# Reference_Voltage.net
KiCad netlist of a schematic drawn in Altium Designer
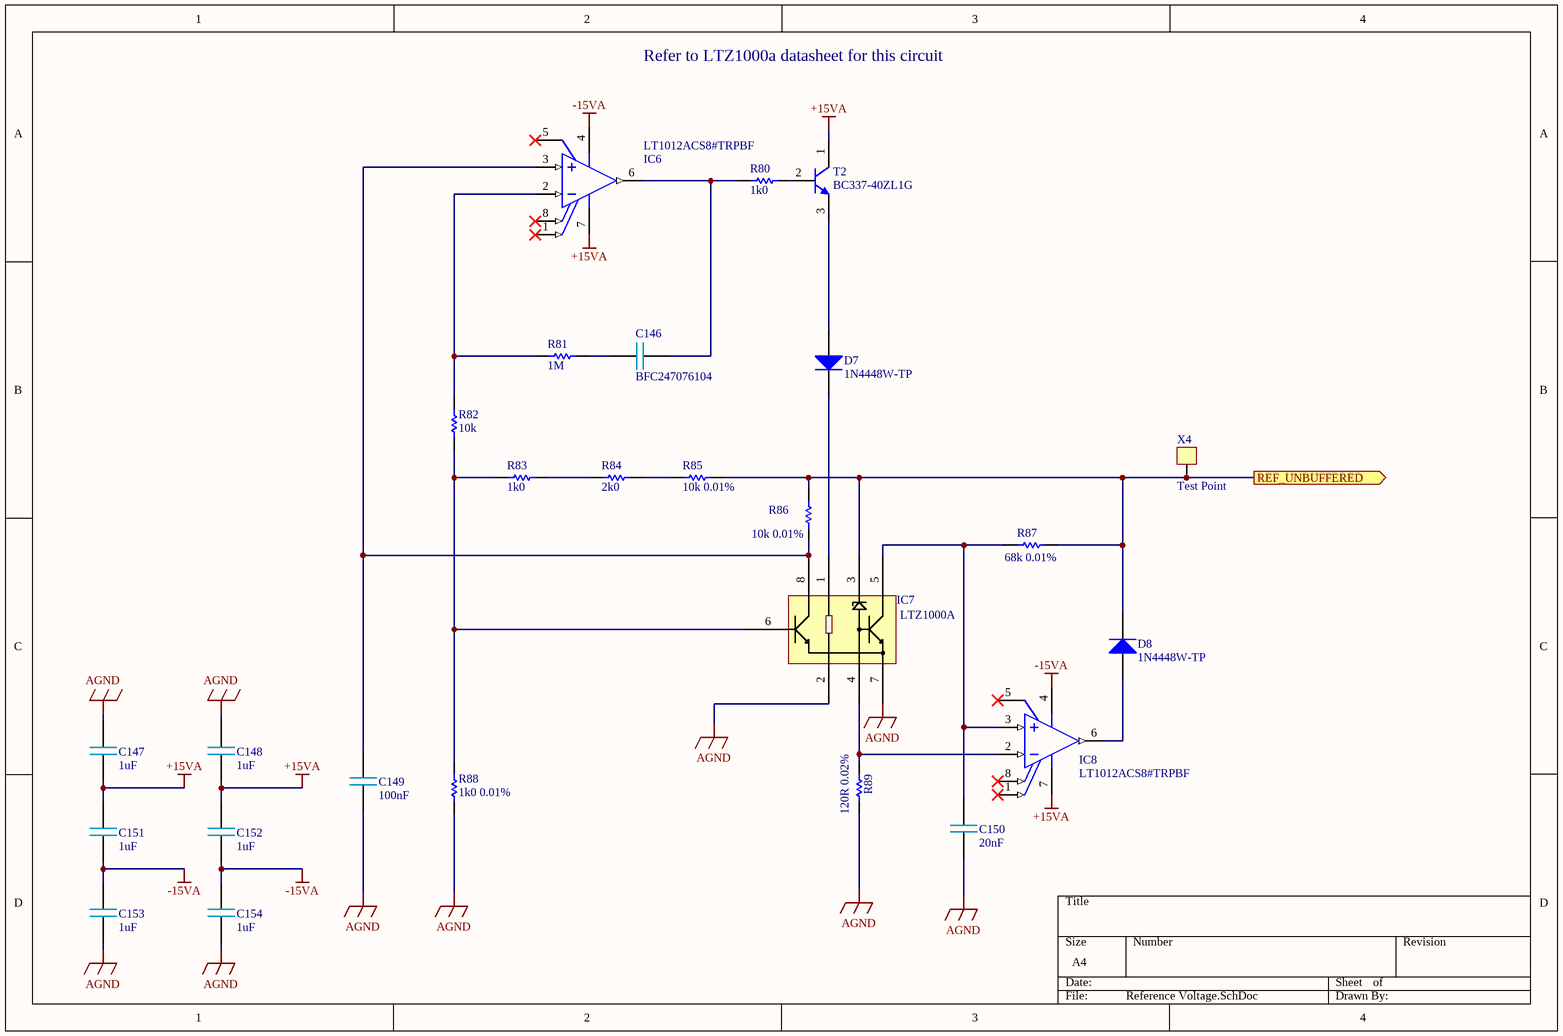
[diagram p0: Reference Voltage.SchDoc]

(export (version "E")
  (design (tool "Eeschema 10.0.6"))
  (components
    (comp (ref "C146")
      (value "BFC247076104")
      (footprint "Cap 5mm polyester")
      (libsource (lib "CurrentSource") (part "BFC247076104"))
    )
    (comp (ref "C147")
      (value "1uF")
      (footprint "Capacitor 7mmx3mm 5mm pitch")
      (libsource (lib "CurrentSource") (part "BFC247076104"))
    )
    (comp (ref "C148")
      (value "1uF")
      (footprint "Capacitor 7mmx3mm 5mm pitch")
      (libsource (lib "CurrentSource") (part "BFC247076104"))
    )
    (comp (ref "C149")
      (value "100nF")
      (footprint "Cap 5mm polyester")
      (libsource (lib "CurrentSource") (part "BFC247076104"))
    )
    (comp (ref "C150")
      (value "20nF")
      (footprint "Cap 5mm polyester")
      (libsource (lib "CurrentSource") (part "BFC247076104"))
    )
    (comp (ref "C151")
      (value "1uF")
      (footprint "Capacitor 7mmx3mm 5mm pitch")
      (libsource (lib "CurrentSource") (part "BFC247076104"))
    )
    (comp (ref "C152")
      (value "1uF")
      (footprint "Capacitor 7mmx3mm 5mm pitch")
      (libsource (lib "CurrentSource") (part "BFC247076104"))
    )
    (comp (ref "C153")
      (value "1uF")
      (footprint "Capacitor 7mmx3mm 5mm pitch")
      (libsource (lib "CurrentSource") (part "BFC247076104"))
    )
    (comp (ref "C154")
      (value "1uF")
      (footprint "Capacitor 7mmx3mm 5mm pitch")
      (libsource (lib "CurrentSource") (part "BFC247076104"))
    )
    (comp (ref "D7")
      (value "1N4448W-TP")
      (footprint "MCC-SOD123_V")
      (description "Switching Diode, 500 mW, 100 V, -55 to 150 degC, SOD123, RoHS, Tape and Reel")
      (fields (field (name "MANUFACTURER") "Micro Commercial Components"))
      (libsource (lib "Altium Content Vault") (part "CMP-0862-00001-1"))
    )
    (comp (ref "D8")
      (value "1N4448W-TP")
      (footprint "MCC-SOD123_V")
      (description "Switching Diode, 500 mW, 100 V, -55 to 150 degC, SOD123, RoHS, Tape and Reel")
      (fields (field (name "MANUFACTURER") "Micro Commercial Components"))
      (libsource (lib "Altium Content Vault") (part "CMP-0862-00001-1"))
    )
    (comp (ref "IC6")
      (value "LT1012ACS8#TRPBF")
      (footprint "LT-S8-8_M")
      (fields
        (field (name "LINEAR TECHNOLOGY PART NUMBER") "LT1012")
        (field (name "MANUFACTURER") "Linear Technology")
      )
      (libsource (lib "Altium Content Vault") (part "CMP-0359-03028-2"))
    )
    (comp (ref "IC7")
      (value "LTZ1000A")
      (footprint "H-08A")
      (libsource (lib "CurrentSource") (part "LTZ1000A"))
    )
    (comp (ref "IC8")
      (value "LT1012ACS8#TRPBF")
      (footprint "LT-S8-8_M")
      (fields
        (field (name "LINEAR TECHNOLOGY PART NUMBER") "LT1012")
        (field (name "MANUFACTURER") "Linear Technology")
      )
      (libsource (lib "Altium Content Vault") (part "CMP-0359-03028-2"))
    )
    (comp (ref "R80")
      (value "1k0")
      (footprint "RESC3116X65X40LL10T20")
      (fields (field (name "MANUFACTURER") "Yageo") (field (name "PART NUMBER") "RC1206FR-0710K2L"))
      (libsource (lib "Altium Content Vault") (part "CMP-2003-03538-1"))
    )
    (comp (ref "R81")
      (value "1M")
      (footprint "RESC0805(2012)_N")
      (description "1M 0.125W 1% 0805 (2012 Metric)  SMD")
      (fields (field (name "POWER") "0.125 W") (field (name "TOLERANCE") "1 %"))
      (libsource (lib "Altium Content Vault") (part "CMP-1013-00849-1"))
    )
    (comp (ref "R82")
      (value "10k")
      (footprint "RESC3116X65X40LL10T20")
      (fields (field (name "MANUFACTURER") "Yageo") (field (name "PART NUMBER") "RC1206FR-0710K2L"))
      (libsource (lib "Altium Content Vault") (part "CMP-2003-03538-1"))
    )
    (comp (ref "R83")
      (value "1k0")
      (footprint "RESC0805(2012)_N")
      (description "1M 0.125W 1% 0805 (2012 Metric)  SMD")
      (fields (field (name "POWER") "0.125 W") (field (name "TOLERANCE") "1 %"))
      (libsource (lib "Altium Content Vault") (part "CMP-1013-00849-1"))
    )
    (comp (ref "R84")
      (value "2k0")
      (footprint "RESC0805(2012)_N")
      (description "1M 0.125W 1% 0805 (2012 Metric)  SMD")
      (fields (field (name "POWER") "0.125 W") (field (name "TOLERANCE") "1 %"))
      (libsource (lib "Altium Content Vault") (part "CMP-1013-00849-1"))
    )
    (comp (ref "R85")
      (value "10k 0.01%")
      (footprint "RESC3116X65X40LL10T20")
      (fields (field (name "MANUFACTURER") "Yageo") (field (name "PART NUMBER") "RC1206FR-0710K2L"))
      (libsource (lib "Altium Content Vault") (part "CMP-2003-03538-1"))
    )
    (comp (ref "R86")
      (value "10k 0.01%")
      (footprint "RESC3116X65X40LL10T20")
      (fields (field (name "MANUFACTURER") "Yageo") (field (name "PART NUMBER") "RC1206FR-0710K2L"))
      (libsource (lib "Altium Content Vault") (part "CMP-2003-03538-1"))
    )
    (comp (ref "R87")
      (value "68k 0.01%")
      (footprint "RESC3116X65X40LL10T20")
      (fields (field (name "MANUFACTURER") "Yageo") (field (name "PART NUMBER") "RC1206FR-0710K2L"))
      (libsource (lib "Altium Content Vault") (part "CMP-2003-03538-1"))
    )
    (comp (ref "R88")
      (value "1k0 0.01%")
      (footprint "RESC3116X65X40LL10T20")
      (fields (field (name "MANUFACTURER") "Yageo") (field (name "PART NUMBER") "RC1206FR-0710K2L"))
      (libsource (lib "Altium Content Vault") (part "CMP-2003-03538-1"))
    )
    (comp (ref "R89")
      (value "120R 0.02%")
      (footprint "RESC3116X65X40LL10T20")
      (fields (field (name "MANUFACTURER") "Yageo") (field (name "PART NUMBER") "RC1206FR-0710K2L"))
      (libsource (lib "Altium Content Vault") (part "CMP-2003-03538-1"))
    )
    (comp (ref "T2")
      (value "BC337-40ZL1G")
      (footprint "ONSC-TO-92-3-29-11_AM_BL")
      (description "Amplifier Transistor, NPN Silicon, 3-Pin TO-92, Pb-Free, Ammo Box")
      (fields (field (name "MANUFACTURER") "On Semiconductor"))
      (libsource (lib "Altium Content Vault") (part "CMP-1048-01583-1"))
    )
    (comp (ref "X4")
      (value "Test Point")
      (footprint "Test Point")
      (libsource (lib "CurrentSource") (part "Test Point"))
    )
  )
  (nets
    (net (code "1") (name "+15VA") (class "Default")
      (node (ref "C147") (pin "2") (pinfunction "2_2") (pintype "passive"))
      (node (ref "C148") (pin "2") (pinfunction "2_2") (pintype "passive"))
      (node (ref "C151") (pin "1") (pinfunction "1_1") (pintype "passive"))
      (node (ref "C152") (pin "1") (pinfunction "1_1") (pintype "passive"))
      (node (ref "IC6") (pin "7") (pinfunction "V+_7") (pintype "power_in"))
      (node (ref "IC8") (pin "7") (pinfunction "V+_7") (pintype "power_in"))
      (node (ref "T2") (pin "1") (pinfunction "C_1") (pintype "passive"))
    )
    (net (code "2") (name "-15VA") (class "Default")
      (node (ref "C151") (pin "2") (pinfunction "2_2") (pintype "passive"))
      (node (ref "C152") (pin "2") (pinfunction "2_2") (pintype "passive"))
      (node (ref "C153") (pin "1") (pinfunction "1_1") (pintype "passive"))
      (node (ref "C154") (pin "1") (pinfunction "1_1") (pintype "passive"))
      (node (ref "IC6") (pin "4") (pinfunction "V-_4") (pintype "power_in"))
      (node (ref "IC8") (pin "4") (pinfunction "V-_4") (pintype "power_in"))
    )
    (net (code "3") (name "/REF_UNBUFFERED") (class "Default")
      (node (ref "D8") (pin "2") (pinfunction "K_2") (pintype "passive"))
      (node (ref "IC7") (pin "3") (pinfunction "3_3") (pintype "passive"))
      (node (ref "R85") (pin "2") (pinfunction "2_2") (pintype "passive"))
      (node (ref "R86") (pin "2") (pinfunction "2_2") (pintype "passive"))
      (node (ref "R87") (pin "1") (pinfunction "1_1") (pintype "passive"))
      (node (ref "X4") (pin "1") (pinfunction "1_1") (pintype "passive"))
    )
    (net (code "4") (name "AGND") (class "Default")
      (node (ref "C147") (pin "1") (pinfunction "1_1") (pintype "passive"))
      (node (ref "C148") (pin "1") (pinfunction "1_1") (pintype "passive"))
      (node (ref "C149") (pin "1") (pinfunction "1_1") (pintype "passive"))
      (node (ref "C150") (pin "1") (pinfunction "1_1") (pintype "passive"))
      (node (ref "C153") (pin "2") (pinfunction "2_2") (pintype "passive"))
      (node (ref "C154") (pin "2") (pinfunction "2_2") (pintype "passive"))
      (node (ref "IC7") (pin "2") (pinfunction "2_2") (pintype "passive"))
      (node (ref "IC7") (pin "7") (pinfunction "7_7") (pintype "passive"))
      (node (ref "R88") (pin "1") (pinfunction "1_1") (pintype "passive"))
      (node (ref "R89") (pin "1") (pinfunction "1_1") (pintype "passive"))
    )
    (net (code "5") (name "Net-(C146-Pad1)") (class "Default")
      (node (ref "C146") (pin "1") (pinfunction "1_1") (pintype "passive"))
      (node (ref "R81") (pin "2") (pinfunction "2_2") (pintype "passive"))
    )
    (net (code "6") (name "Net-(D7-A)") (class "Default")
      (node (ref "D7") (pin "1") (pinfunction "A_1") (pintype "passive"))
      (node (ref "T2") (pin "3") (pinfunction "E_3") (pintype "passive"))
    )
    (net (code "7") (name "Net-(D7-K)") (class "Default")
      (node (ref "D7") (pin "2") (pinfunction "K_2") (pintype "passive"))
      (node (ref "IC7") (pin "1") (pinfunction "1_1") (pintype "passive"))
    )
    (net (code "8") (name "Net-(D8-A)") (class "Default")
      (node (ref "D8") (pin "1") (pinfunction "A_1") (pintype "passive"))
      (node (ref "IC8") (pin "6") (pinfunction "OUT_6") (pintype "output"))
    )
    (net (code "9") (name "Net-(IC6-+IN)") (class "Default")
      (node (ref "C149") (pin "2") (pinfunction "2_2") (pintype "passive"))
      (node (ref "IC6") (pin "3") (pinfunction "+IN_3") (pintype "input"))
      (node (ref "IC7") (pin "8") (pinfunction "8_8") (pintype "passive"))
      (node (ref "R86") (pin "1") (pinfunction "1_1") (pintype "passive"))
    )
    (net (code "10") (name "Net-(IC6--IN)") (class "Default")
      (node (ref "IC6") (pin "2") (pinfunction "-IN_2") (pintype "input"))
      (node (ref "R81") (pin "1") (pinfunction "1_1") (pintype "passive"))
      (node (ref "R82") (pin "1") (pinfunction "1_1") (pintype "passive"))
    )
    (net (code "11") (name "Net-(IC6-OUT)") (class "Default")
      (node (ref "C146") (pin "2") (pinfunction "2_2") (pintype "passive"))
      (node (ref "IC6") (pin "6") (pinfunction "OUT_6") (pintype "output"))
      (node (ref "R80") (pin "1") (pinfunction "1_1") (pintype "passive"))
    )
    (net (code "12") (name "Net-(IC7-Pad6)") (class "Default")
      (node (ref "IC7") (pin "6") (pinfunction "6_6") (pintype "passive"))
      (node (ref "R82") (pin "2") (pinfunction "2_2") (pintype "passive"))
      (node (ref "R83") (pin "1") (pinfunction "1_1") (pintype "passive"))
      (node (ref "R88") (pin "2") (pinfunction "2_2") (pintype "passive"))
    )
    (net (code "13") (name "Net-(IC8-+IN)") (class "Default")
      (node (ref "C150") (pin "2") (pinfunction "2_2") (pintype "passive"))
      (node (ref "IC7") (pin "5") (pinfunction "5_5") (pintype "passive"))
      (node (ref "IC8") (pin "3") (pinfunction "+IN_3") (pintype "input"))
      (node (ref "R87") (pin "2") (pinfunction "2_2") (pintype "passive"))
    )
    (net (code "14") (name "Net-(IC8--IN)") (class "Default")
      (node (ref "IC7") (pin "4") (pinfunction "4_4") (pintype "passive"))
      (node (ref "IC8") (pin "2") (pinfunction "-IN_2") (pintype "input"))
      (node (ref "R89") (pin "2") (pinfunction "2_2") (pintype "passive"))
    )
    (net (code "15") (name "Net-(R83-Pad2)") (class "Default")
      (node (ref "R83") (pin "2") (pinfunction "2_2") (pintype "passive"))
      (node (ref "R84") (pin "1") (pinfunction "1_1") (pintype "passive"))
    )
    (net (code "16") (name "Net-(R84-Pad2)") (class "Default")
      (node (ref "R84") (pin "2") (pinfunction "2_2") (pintype "passive"))
      (node (ref "R85") (pin "1") (pinfunction "1_1") (pintype "passive"))
    )
    (net (code "17") (name "Net-(T2-B)") (class "Default")
      (node (ref "R80") (pin "2") (pinfunction "2_2") (pintype "passive"))
      (node (ref "T2") (pin "2") (pinfunction "B_2") (pintype "passive"))
    )
    (net (code "18") (name "unconnected-(IC6-OVER_COMP-Pad5)") (class "Default")
      (node (ref "IC6") (pin "5") (pinfunction "OVER_COMP_5") (pintype "passive+no_connect"))
    )
    (net (code "19") (name "unconnected-(IC6-VOS_TRIM-Pad1)") (class "Default")
      (node (ref "IC6") (pin "1") (pinfunction "VOS_TRIM_1") (pintype "input+no_connect"))
    )
    (net (code "20") (name "unconnected-(IC6-VOS_TRIM-Pad8)") (class "Default")
      (node (ref "IC6") (pin "8") (pinfunction "VOS_TRIM_8") (pintype "input+no_connect"))
    )
    (net (code "21") (name "unconnected-(IC8-OVER_COMP-Pad5)") (class "Default")
      (node (ref "IC8") (pin "5") (pinfunction "OVER_COMP_5") (pintype "passive+no_connect"))
    )
    (net (code "22") (name "unconnected-(IC8-VOS_TRIM-Pad1)") (class "Default")
      (node (ref "IC8") (pin "1") (pinfunction "VOS_TRIM_1") (pintype "input+no_connect"))
    )
    (net (code "23") (name "unconnected-(IC8-VOS_TRIM-Pad8)") (class "Default")
      (node (ref "IC8") (pin "8") (pinfunction "VOS_TRIM_8") (pintype "input+no_connect"))
    )
  )
)
